# RFID_MFRC522.net
KiCad netlist of a schematic drawn in EAGLE
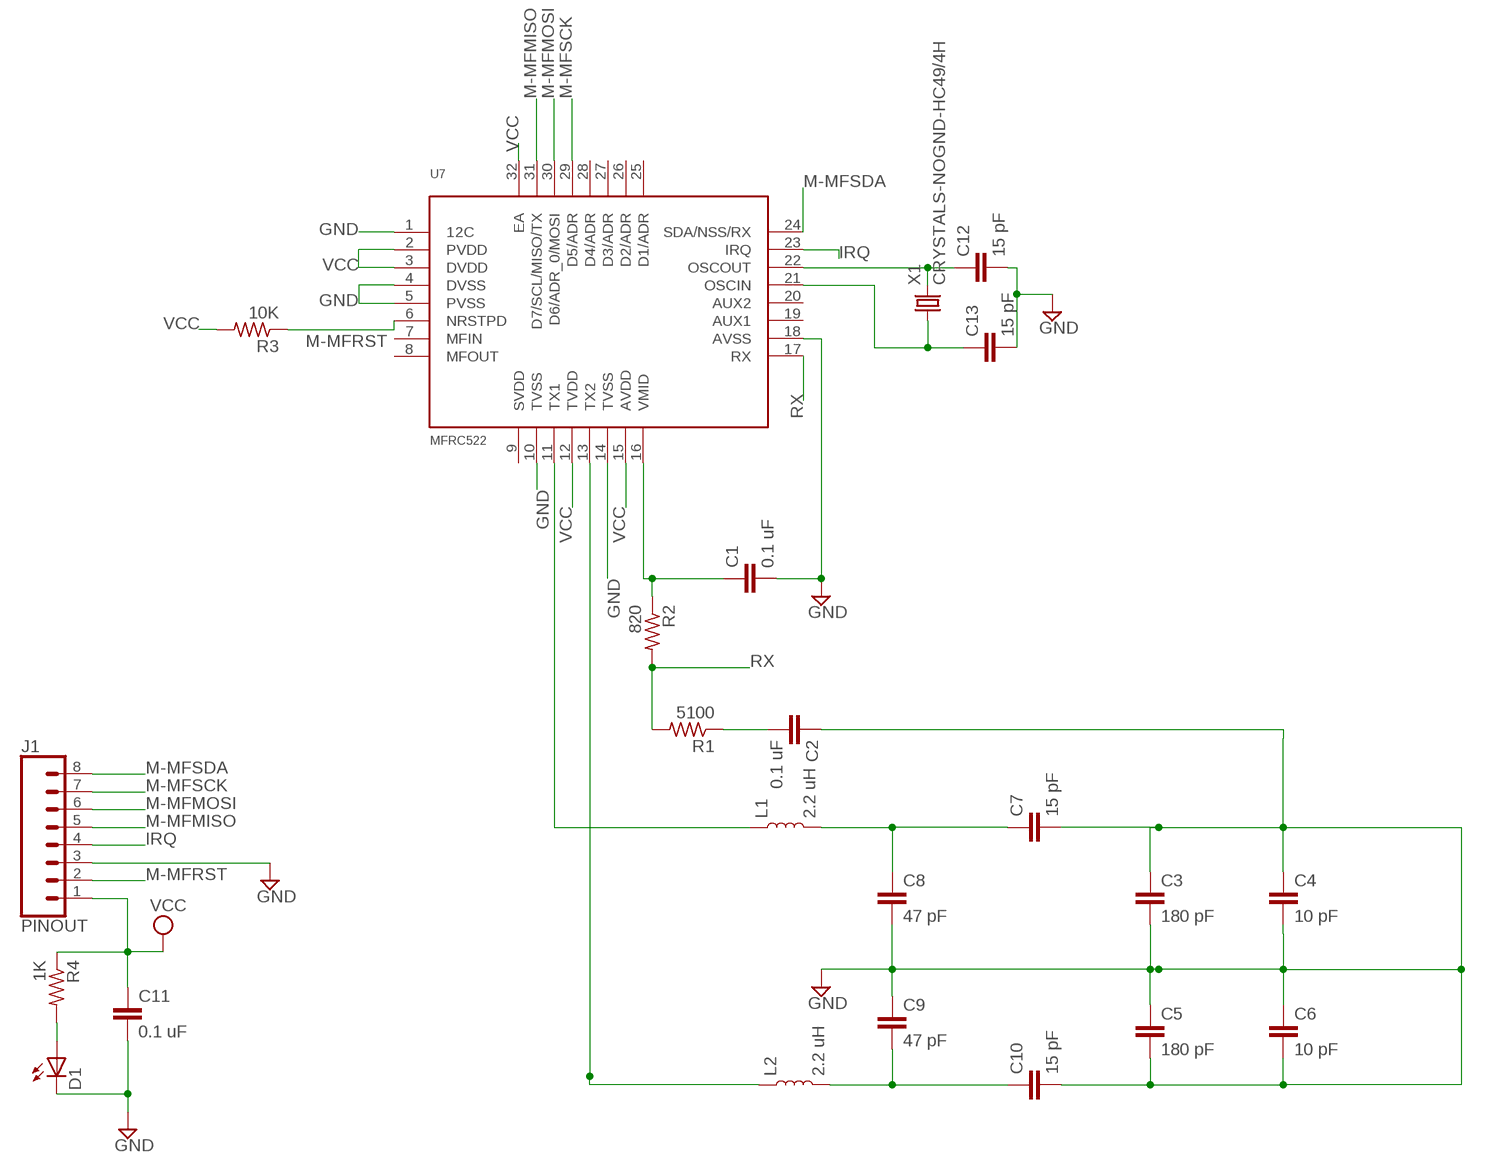
[diagram p0: schematic, sheet 1]

(export (version "E")
  (design (tool "Eeschema 10.0.6"))
  (components
    (comp (ref "C1")
      (value "0.1 uF")
      (footprint "eagle-import:C0603")
      (libsource (lib "eagle-import") (part "C-EUC0603"))
    )
    (comp (ref "C2")
      (value "0.1 uF")
      (footprint "eagle-import:C0603")
      (libsource (lib "eagle-import") (part "C-EUC0603"))
    )
    (comp (ref "C3")
      (value "180 pF")
      (footprint "eagle-import:C0603")
      (libsource (lib "eagle-import") (part "C-EUC0603"))
    )
    (comp (ref "C4")
      (value "10 pF")
      (footprint "eagle-import:C0603")
      (libsource (lib "eagle-import") (part "C-EUC0603"))
    )
    (comp (ref "C5")
      (value "180 pF")
      (footprint "eagle-import:C0603")
      (libsource (lib "eagle-import") (part "C-EUC0603"))
    )
    (comp (ref "C6")
      (value "10 pF")
      (footprint "eagle-import:C0603")
      (libsource (lib "eagle-import") (part "C-EUC0603"))
    )
    (comp (ref "C7")
      (value "15 pF")
      (footprint "eagle-import:C0603")
      (libsource (lib "eagle-import") (part "C-EUC0603"))
    )
    (comp (ref "C8")
      (value "47 pF")
      (footprint "eagle-import:C0603")
      (libsource (lib "eagle-import") (part "C-EUC0603"))
    )
    (comp (ref "C9")
      (value "47 pF")
      (footprint "eagle-import:C0603")
      (libsource (lib "eagle-import") (part "C-EUC0603"))
    )
    (comp (ref "C10")
      (value "15 pF")
      (footprint "eagle-import:C0603")
      (libsource (lib "eagle-import") (part "C-EUC0603"))
    )
    (comp (ref "C11")
      (value "0.1 uF")
      (footprint "eagle-import:C0603")
      (libsource (lib "eagle-import") (part "C-EUC0603"))
    )
    (comp (ref "C12")
      (value "15 pF")
      (footprint "eagle-import:C0603")
      (libsource (lib "eagle-import") (part "C-EUC0603"))
    )
    (comp (ref "C13")
      (value "15 pF")
      (footprint "eagle-import:C0603")
      (libsource (lib "eagle-import") (part "C-EUC0603"))
    )
    (comp (ref "D1")
      (value "LED")
      (footprint "eagle-import:C1210")
      (libsource (lib "eagle-import") (part "LED"))
    )
    (comp (ref "J1")
      (value "PINOUT")
      (footprint "eagle-import:1X08_NO_SILK")
      (libsource (lib "eagle-import") (part "CONN_08NO_SILK_FEMALE_PTH"))
    )
    (comp (ref "L1")
      (value "2.2 uH")
      (footprint "eagle-import:0603")
      (libsource (lib "eagle-import") (part "INDUCTOR-0603-33NH"))
    )
    (comp (ref "L2")
      (value "2.2 uH")
      (footprint "eagle-import:0603")
      (libsource (lib "eagle-import") (part "INDUCTOR-0603-33NH"))
    )
    (comp (ref "R1")
      (value "5100")
      (footprint "eagle-import:R0603")
      (libsource (lib "eagle-import") (part "R-US_R0603"))
    )
    (comp (ref "R2")
      (value "820")
      (footprint "eagle-import:R0603")
      (libsource (lib "eagle-import") (part "R-US_R0603"))
    )
    (comp (ref "R3")
      (value "10K")
      (footprint "eagle-import:R0603")
      (libsource (lib "eagle-import") (part "R-US_R0603"))
    )
    (comp (ref "R4")
      (value "1K")
      (footprint "eagle-import:R0603")
      (libsource (lib "eagle-import") (part "R-US_R0603"))
    )
    (comp (ref "U7")
      (value "MFRC522")
      (footprint "eagle-import:MFR522")
      (libsource (lib "eagle-import") (part "MFRC522"))
    )
    (comp (ref "X1")
      (value "CRYSTALS-NOGND-HC49/4H")
      (footprint "eagle-import:HC49")
      (libsource (lib "eagle-import") (part "CRYSTALS-NOGND-HC49/4H"))
    )
  )
  (nets
    (net (code "1") (name "/IRQ") (class "Default")
      (node (ref "J1") (pin "4") (pinfunction "4_4") (pintype "passive"))
      (node (ref "U7") (pin "23") (pinfunction "IRQ_23") (pintype "bidirectional"))
    )
    (net (code "2") (name "/M-MFMISO") (class "Default")
      (node (ref "J1") (pin "5") (pinfunction "5_5") (pintype "passive"))
      (node (ref "U7") (pin "31") (pinfunction "D7/SCL/MISO/TX_31") (pintype "bidirectional"))
    )
    (net (code "3") (name "/M-MFMOSI") (class "Default")
      (node (ref "J1") (pin "6") (pinfunction "6_6") (pintype "passive"))
      (node (ref "U7") (pin "30") (pinfunction "D6/ADR_0/MOSI_30") (pintype "bidirectional"))
    )
    (net (code "4") (name "/M-MFRST") (class "Default")
      (node (ref "J1") (pin "2") (pinfunction "2_2") (pintype "passive"))
      (node (ref "R3") (pin "1") (pinfunction "1_1") (pintype "passive"))
      (node (ref "U7") (pin "6") (pinfunction "NRSTPD_6") (pintype "bidirectional"))
    )
    (net (code "5") (name "/M-MFSCK") (class "Default")
      (node (ref "J1") (pin "7") (pinfunction "7_7") (pintype "passive"))
      (node (ref "U7") (pin "29") (pinfunction "D5/ADR_29") (pintype "bidirectional"))
    )
    (net (code "6") (name "/M-MFSDA") (class "Default")
      (node (ref "J1") (pin "8") (pinfunction "8_8") (pintype "passive"))
      (node (ref "U7") (pin "24") (pinfunction "SDA/NSS/RX_24") (pintype "bidirectional"))
    )
    (net (code "7") (name "/RX") (class "Default")
      (node (ref "R1") (pin "2") (pinfunction "2_2") (pintype "passive"))
      (node (ref "R2") (pin "2") (pinfunction "2_2") (pintype "passive"))
      (node (ref "U7") (pin "17") (pinfunction "RX_17") (pintype "bidirectional"))
    )
    (net (code "8") (name "GND") (class "Default")
      (node (ref "C1") (pin "2") (pinfunction "2_2") (pintype "passive"))
      (node (ref "C10") (pin "2") (pinfunction "2_2") (pintype "passive"))
      (node (ref "C11") (pin "2") (pinfunction "2_2") (pintype "passive"))
      (node (ref "C12") (pin "2") (pinfunction "2_2") (pintype "passive"))
      (node (ref "C13") (pin "2") (pinfunction "2_2") (pintype "passive"))
      (node (ref "C2") (pin "1") (pinfunction "1_1") (pintype "passive"))
      (node (ref "C3") (pin "1") (pinfunction "1_1") (pintype "passive"))
      (node (ref "C3") (pin "2") (pinfunction "2_2") (pintype "passive"))
      (node (ref "C4") (pin "1") (pinfunction "1_1") (pintype "passive"))
      (node (ref "C4") (pin "2") (pinfunction "2_2") (pintype "passive"))
      (node (ref "C5") (pin "1") (pinfunction "1_1") (pintype "passive"))
      (node (ref "C5") (pin "2") (pinfunction "2_2") (pintype "passive"))
      (node (ref "C6") (pin "1") (pinfunction "1_1") (pintype "passive"))
      (node (ref "C6") (pin "2") (pinfunction "2_2") (pintype "passive"))
      (node (ref "C7") (pin "2") (pinfunction "2_2") (pintype "passive"))
      (node (ref "C8") (pin "2") (pinfunction "2_2") (pintype "passive"))
      (node (ref "C9") (pin "1") (pinfunction "1_1") (pintype "passive"))
      (node (ref "D1") (pin "C") (pinfunction "C_C") (pintype "passive"))
      (node (ref "J1") (pin "3") (pinfunction "3_3") (pintype "passive"))
      (node (ref "U7") (pin "1") (pinfunction "12C_1") (pintype "bidirectional"))
      (node (ref "U7") (pin "10") (pinfunction "TVSS_10") (pintype "bidirectional"))
      (node (ref "U7") (pin "14") (pinfunction "TVSS_14") (pintype "bidirectional"))
      (node (ref "U7") (pin "18") (pinfunction "AVSS_18") (pintype "bidirectional"))
      (node (ref "U7") (pin "4") (pinfunction "DVSS_4") (pintype "bidirectional"))
      (node (ref "U7") (pin "5") (pinfunction "PVSS_5") (pintype "bidirectional"))
    )
    (net (code "9") (name "Net-(C2-Pad2)") (class "Default")
      (node (ref "C2") (pin "2") (pinfunction "2_2") (pintype "passive"))
      (node (ref "R1") (pin "1") (pinfunction "1_1") (pintype "passive"))
    )
    (net (code "10") (name "Net-(C7-Pad1)") (class "Default")
      (node (ref "C7") (pin "1") (pinfunction "1_1") (pintype "passive"))
      (node (ref "C8") (pin "1") (pinfunction "1_1") (pintype "passive"))
      (node (ref "L1") (pin "2") (pinfunction "2_2") (pintype "passive"))
    )
    (net (code "11") (name "Net-(C10-Pad1)") (class "Default")
      (node (ref "C10") (pin "1") (pinfunction "1_1") (pintype "passive"))
      (node (ref "C9") (pin "2") (pinfunction "2_2") (pintype "passive"))
      (node (ref "L2") (pin "2") (pinfunction "2_2") (pintype "passive"))
    )
    (net (code "12") (name "Net-(D1-PadA)") (class "Default")
      (node (ref "D1") (pin "A") (pinfunction "A_A") (pintype "passive"))
      (node (ref "R4") (pin "2") (pinfunction "2_2") (pintype "passive"))
    )
    (net (code "13") (name "Net-(U7-OSCIN)") (class "Default")
      (node (ref "C13") (pin "1") (pinfunction "1_1") (pintype "passive"))
      (node (ref "U7") (pin "21") (pinfunction "OSCIN_21") (pintype "bidirectional"))
      (node (ref "X1") (pin "1") (pinfunction "1_1") (pintype "passive"))
    )
    (net (code "14") (name "Net-(U7-OSCOUT)") (class "Default")
      (node (ref "C12") (pin "1") (pinfunction "1_1") (pintype "passive"))
      (node (ref "U7") (pin "22") (pinfunction "OSCOUT_22") (pintype "bidirectional"))
      (node (ref "X1") (pin "2") (pinfunction "2_2") (pintype "passive"))
    )
    (net (code "15") (name "Net-(U7-TX1)") (class "Default")
      (node (ref "L1") (pin "1") (pinfunction "1_1") (pintype "passive"))
      (node (ref "U7") (pin "11") (pinfunction "TX1_11") (pintype "bidirectional"))
    )
    (net (code "16") (name "Net-(U7-TX2)") (class "Default")
      (node (ref "L2") (pin "1") (pinfunction "1_1") (pintype "passive"))
      (node (ref "U7") (pin "13") (pinfunction "TX2_13") (pintype "bidirectional"))
    )
    (net (code "17") (name "Net-(U7-VMID)") (class "Default")
      (node (ref "C1") (pin "1") (pinfunction "1_1") (pintype "passive"))
      (node (ref "R2") (pin "1") (pinfunction "1_1") (pintype "passive"))
      (node (ref "U7") (pin "16") (pinfunction "VMID_16") (pintype "bidirectional"))
    )
    (net (code "18") (name "VCC") (class "Default")
      (node (ref "C11") (pin "1") (pinfunction "1_1") (pintype "passive"))
      (node (ref "J1") (pin "1") (pinfunction "1_1") (pintype "passive"))
      (node (ref "R3") (pin "2") (pinfunction "2_2") (pintype "passive"))
      (node (ref "R4") (pin "1") (pinfunction "1_1") (pintype "passive"))
      (node (ref "U7") (pin "12") (pinfunction "TVDD_12") (pintype "bidirectional"))
      (node (ref "U7") (pin "15") (pinfunction "AVDD_15") (pintype "bidirectional"))
      (node (ref "U7") (pin "2") (pinfunction "PVDD_2") (pintype "bidirectional"))
      (node (ref "U7") (pin "3") (pinfunction "DVDD_3") (pintype "bidirectional"))
      (node (ref "U7") (pin "32") (pinfunction "EA_32") (pintype "bidirectional"))
    )
    (net (code "19") (name "unconnected-(U7-AUX1-Pad19)") (class "Default")
      (node (ref "U7") (pin "19") (pinfunction "AUX1_19") (pintype "bidirectional"))
    )
    (net (code "20") (name "unconnected-(U7-AUX2-Pad20)") (class "Default")
      (node (ref "U7") (pin "20") (pinfunction "AUX2_20") (pintype "bidirectional"))
    )
    (net (code "21") (name "unconnected-(U7-D1{slash}ADR-Pad25)") (class "Default")
      (node (ref "U7") (pin "25") (pinfunction "D1/ADR_25") (pintype "bidirectional"))
    )
    (net (code "22") (name "unconnected-(U7-D2{slash}ADR-Pad26)") (class "Default")
      (node (ref "U7") (pin "26") (pinfunction "D2/ADR_26") (pintype "bidirectional"))
    )
    (net (code "23") (name "unconnected-(U7-D3{slash}ADR-Pad27)") (class "Default")
      (node (ref "U7") (pin "27") (pinfunction "D3/ADR_27") (pintype "bidirectional"))
    )
    (net (code "24") (name "unconnected-(U7-D4{slash}ADR-Pad28)") (class "Default")
      (node (ref "U7") (pin "28") (pinfunction "D4/ADR_28") (pintype "bidirectional"))
    )
    (net (code "25") (name "unconnected-(U7-MFIN-Pad7)") (class "Default")
      (node (ref "U7") (pin "7") (pinfunction "MFIN_7") (pintype "bidirectional"))
    )
    (net (code "26") (name "unconnected-(U7-MFOUT-Pad8)") (class "Default")
      (node (ref "U7") (pin "8") (pinfunction "MFOUT_8") (pintype "bidirectional"))
    )
    (net (code "27") (name "unconnected-(U7-SVDD-Pad9)") (class "Default")
      (node (ref "U7") (pin "9") (pinfunction "SVDD_9") (pintype "bidirectional"))
    )
  )
)
